# IFX9201_Core.net
KiCad netlist of a schematic drawn in Altium Designer
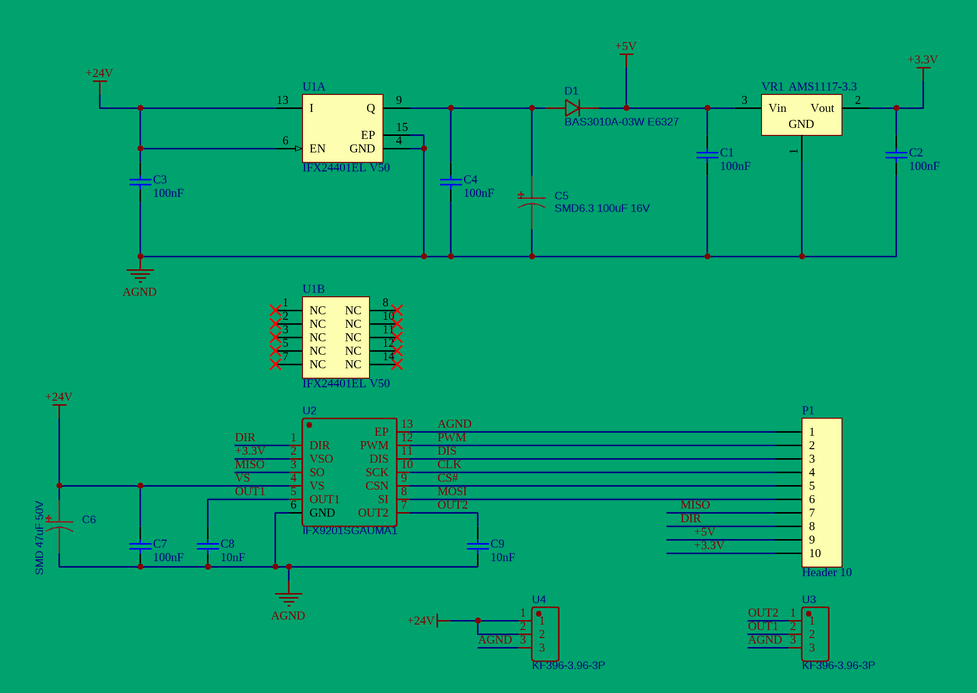
[diagram p0: IFX9201_Core.SchDoc]

(export (version "E")
  (design (tool "Eeschema 10.0.6"))
  (components
    (comp (ref "C1")
      (value "100nF")
      (footprint "0603_C")
      (description "GCJ188R72A104KA01D")
      (libsource (lib "Miscellaneous Devices LC") (part "0603 2.7nF (272) 10% 50V"))
    )
    (comp (ref "C2")
      (value "100nF")
      (footprint "0603_C")
      (description "GCJ188R72A104KA01D")
      (libsource (lib "Miscellaneous Devices LC") (part "0603 2.7nF (272) 10% 50V"))
    )
    (comp (ref "C3")
      (value "100nF")
      (footprint "0603_C")
      (description "GCJ188R72A104KA01D")
      (libsource (lib "Miscellaneous Devices LC") (part "0603 2.7nF (272) 10% 50V"))
    )
    (comp (ref "C4")
      (value "100nF")
      (footprint "0603_C")
      (description "GCJ188R72A104KA01D")
      (libsource (lib "Miscellaneous Devices LC") (part "0603 2.7nF (272) 10% 50V"))
    )
    (comp (ref "C5")
      (value "SMD6.3 100uF 16V")
      (footprint "CAP-SMD_BD6.3-L6.6-W6.6-FD")
      (description "UUD1C101MCL1GS")
      (libsource (lib "Miscellaneous Devices LC") (part "SMD6.3 100uF"))
    )
    (comp (ref "C6")
      (value "SMD 47uF 50V")
      (footprint "CAP-SMD_BD6.3-L6.6-W6.6-FD")
      (description "EEEFT1H470AP")
      (libsource (lib "Miscellaneous Devices LC") (part "SMD6.3 100uF"))
    )
    (comp (ref "C7")
      (value "100nF")
      (footprint "0603_C")
      (description "GCJ188R72A104KA01D")
      (libsource (lib "Miscellaneous Devices LC") (part "0603 2.7nF (272) 10% 50V"))
    )
    (comp (ref "C8")
      (value "10nF")
      (footprint "0603_C")
      (description "GCM188R72A103KA37D")
      (libsource (lib "Miscellaneous Devices LC") (part "0603 2.7nF (272) 10% 50V"))
    )
    (comp (ref "C9")
      (value "10nF")
      (footprint "0603_C")
      (description "GCM188R72A103KA37D")
      (libsource (lib "Miscellaneous Devices LC") (part "0603 2.7nF (272) 10% 50V"))
    )
    (comp (ref "D1")
      (value "BAS3010A-03W E6327")
      (footprint "SOD-323_L1.8-W1.3-LS2.5-RD")
      (fields (field (name "BOM_MANUFACTURER PART") "BAS 3010A-03W E6327"))
      (libsource (lib "Miscellaneous Devices LC") (part "BAS3010A-03W E6327"))
    )
    (comp (ref "P1")
      (value "Header 10")
      (footprint "HDR1X10")
      (description "Header, 10-Pin")
      (fields (field (name "PUBLISHER") "Altium Limited"))
      (libsource (lib "Miscellaneous Connectors") (part "Header 10"))
    )
    (comp (ref "U1")
      (value "IFX24401EL V50")
      (footprint "INF-PG-SSOP-14-1_N")
      (fields (field (name "MANUFACTURER") "Infineon"))
      (libsource (lib "Infineon_Power_Supply_Voltage_Regulator") (part "IFX24401EL V50"))
    )
    (comp (ref "U2")
      (value "IFX9201SGAUMA1")
      (footprint "SO-12_L6.4-W7.5-P1.00-LS10.3-BL-EP")
      (libsource (lib "Miscellaneous Devices LC") (part "IFX9201SGAUMA1"))
    )
    (comp (ref "U3")
      (value "KF396-3.96-3P")
      (footprint "CONN-TH_3P-P3.96_KF396-3.96-3P")
      (fields (field (name "BOM_SUPPLIER PART") "C474895") (field (name "CONTRIBUTOR") "LCSC"))
      (libsource (lib "Miscellaneous Devices LC") (part "KF396-3.96-3P"))
    )
    (comp (ref "U4")
      (value "KF396-3.96-3P")
      (footprint "CONN-TH_3P-P3.96_KF396-3.96-3P")
      (fields (field (name "BOM_SUPPLIER PART") "C474895") (field (name "CONTRIBUTOR") "LCSC"))
      (libsource (lib "Miscellaneous Devices LC") (part "KF396-3.96-3P"))
    )
    (comp (ref "VR1")
      (value "AMS1117-3.3")
      (footprint "SOT-223")
      (description "低压差线性稳压(LDO)")
      (libsource (lib "Miscellaneous Devices LC") (part "SOT-223 AMS1117-3.3"))
    )
  )
  (nets
    (net (code "1") (name "+3.3V") (class "Default")
      (node (ref "C2") (pin "2") (pinfunction "2_2") (pintype "passive"))
      (node (ref "P1") (pin "10") (pinfunction "10_10") (pintype "passive"))
      (node (ref "U2") (pin "2") (pinfunction "VSO_2") (pintype "passive"))
      (node (ref "VR1") (pin "2") (pinfunction "Vout_2") (pintype "passive"))
    )
    (net (code "2") (name "+5V") (class "Default")
      (node (ref "C1") (pin "2") (pinfunction "2_2") (pintype "passive"))
      (node (ref "D1") (pin "1") (pinfunction "C_1") (pintype "passive"))
      (node (ref "P1") (pin "9") (pinfunction "9_9") (pintype "passive"))
      (node (ref "VR1") (pin "3") (pinfunction "Vin_3") (pintype "passive"))
    )
    (net (code "3") (name "+24V") (class "Default")
      (node (ref "C3") (pin "2") (pinfunction "2_2") (pintype "passive"))
      (node (ref "C6") (pin "1") (pinfunction "1_1") (pintype "passive"))
      (node (ref "C7") (pin "2") (pinfunction "2_2") (pintype "passive"))
      (node (ref "U1") (pin "13") (pinfunction "I_13") (pintype "power_in"))
      (node (ref "U1") (pin "6") (pinfunction "EN_6") (pintype "input"))
      (node (ref "U2") (pin "4") (pinfunction "VS_4") (pintype "passive"))
      (node (ref "U4") (pin "1") (pinfunction "1_1") (pintype "passive"))
      (node (ref "U4") (pin "2") (pinfunction "2_2") (pintype "passive"))
    )
    (net (code "4") (name "/CLK") (class "Default")
      (node (ref "P1") (pin "4") (pinfunction "4_4") (pintype "passive"))
      (node (ref "U2") (pin "10") (pinfunction "SCK_10") (pintype "passive"))
    )
    (net (code "5") (name "/CS#") (class "Default")
      (node (ref "P1") (pin "5") (pinfunction "5_5") (pintype "passive"))
      (node (ref "U2") (pin "9") (pinfunction "CSN_9") (pintype "passive"))
    )
    (net (code "6") (name "/DIR") (class "Default")
      (node (ref "P1") (pin "8") (pinfunction "8_8") (pintype "passive"))
      (node (ref "U2") (pin "1") (pinfunction "DIR_1") (pintype "passive"))
    )
    (net (code "7") (name "/DIS") (class "Default")
      (node (ref "P1") (pin "3") (pinfunction "3_3") (pintype "passive"))
      (node (ref "U2") (pin "11") (pinfunction "DIS_11") (pintype "passive"))
    )
    (net (code "8") (name "/MISO") (class "Default")
      (node (ref "P1") (pin "7") (pinfunction "7_7") (pintype "passive"))
      (node (ref "U2") (pin "3") (pinfunction "SO_3") (pintype "passive"))
    )
    (net (code "9") (name "/MOSI") (class "Default")
      (node (ref "P1") (pin "6") (pinfunction "6_6") (pintype "passive"))
      (node (ref "U2") (pin "8") (pinfunction "SI_8") (pintype "passive"))
    )
    (net (code "10") (name "/OUT1") (class "Default")
      (node (ref "C8") (pin "2") (pinfunction "2_2") (pintype "passive"))
      (node (ref "U2") (pin "5") (pinfunction "OUT1_5") (pintype "passive"))
      (node (ref "U3") (pin "2") (pinfunction "2_2") (pintype "passive"))
    )
    (net (code "11") (name "/OUT2") (class "Default")
      (node (ref "C9") (pin "2") (pinfunction "2_2") (pintype "passive"))
      (node (ref "U2") (pin "7") (pinfunction "OUT2_7") (pintype "passive"))
      (node (ref "U3") (pin "1") (pinfunction "1_1") (pintype "passive"))
    )
    (net (code "12") (name "/PWM") (class "Default")
      (node (ref "P1") (pin "2") (pinfunction "2_2") (pintype "passive"))
      (node (ref "U2") (pin "12") (pinfunction "PWM_12") (pintype "passive"))
    )
    (net (code "13") (name "AGND") (class "Default")
      (node (ref "C1") (pin "1") (pinfunction "1_1") (pintype "passive"))
      (node (ref "C2") (pin "1") (pinfunction "1_1") (pintype "passive"))
      (node (ref "C3") (pin "1") (pinfunction "1_1") (pintype "passive"))
      (node (ref "C4") (pin "1") (pinfunction "1_1") (pintype "passive"))
      (node (ref "C5") (pin "2") (pinfunction "2_2") (pintype "passive"))
      (node (ref "C6") (pin "2") (pinfunction "2_2") (pintype "passive"))
      (node (ref "C7") (pin "1") (pinfunction "1_1") (pintype "passive"))
      (node (ref "C8") (pin "1") (pinfunction "1_1") (pintype "passive"))
      (node (ref "C9") (pin "1") (pinfunction "1_1") (pintype "passive"))
      (node (ref "P1") (pin "1") (pinfunction "1_1") (pintype "passive"))
      (node (ref "U1") (pin "15") (pinfunction "EP_15") (pintype "power_in"))
      (node (ref "U1") (pin "4") (pinfunction "GND_4") (pintype "power_in"))
      (node (ref "U2") (pin "13") (pinfunction "EP_13") (pintype "passive"))
      (node (ref "U2") (pin "6") (pinfunction "GND_6") (pintype "passive"))
      (node (ref "U3") (pin "3") (pinfunction "3_3") (pintype "passive"))
      (node (ref "U4") (pin "3") (pinfunction "3_3") (pintype "passive"))
      (node (ref "VR1") (pin "1") (pinfunction "GND_1") (pintype "passive"))
    )
    (net (code "14") (name "Net-(D1-A)") (class "Default")
      (node (ref "C4") (pin "2") (pinfunction "2_2") (pintype "passive"))
      (node (ref "C5") (pin "1") (pinfunction "1_1") (pintype "passive"))
      (node (ref "D1") (pin "2") (pinfunction "A_2") (pintype "passive"))
      (node (ref "U1") (pin "9") (pinfunction "Q_9") (pintype "power_in"))
    )
    (net (code "15") (name "unconnected-(U1B-NC-Pad1)") (class "Default")
      (node (ref "U1") (pin "1") (pinfunction "NC_1") (pintype "passive+no_connect"))
    )
    (net (code "16") (name "unconnected-(U1B-NC-Pad2)") (class "Default")
      (node (ref "U1") (pin "2") (pinfunction "NC_2") (pintype "passive+no_connect"))
    )
    (net (code "17") (name "unconnected-(U1B-NC-Pad3)") (class "Default")
      (node (ref "U1") (pin "3") (pinfunction "NC_3") (pintype "passive+no_connect"))
    )
    (net (code "18") (name "unconnected-(U1B-NC-Pad5)") (class "Default")
      (node (ref "U1") (pin "5") (pinfunction "NC_5") (pintype "passive+no_connect"))
    )
    (net (code "19") (name "unconnected-(U1B-NC-Pad7)") (class "Default")
      (node (ref "U1") (pin "7") (pinfunction "NC_7") (pintype "passive+no_connect"))
    )
    (net (code "20") (name "unconnected-(U1B-NC-Pad8)") (class "Default")
      (node (ref "U1") (pin "8") (pinfunction "NC_8") (pintype "passive+no_connect"))
    )
    (net (code "21") (name "unconnected-(U1B-NC-Pad10)") (class "Default")
      (node (ref "U1") (pin "10") (pinfunction "NC_10") (pintype "passive+no_connect"))
    )
    (net (code "22") (name "unconnected-(U1B-NC-Pad11)") (class "Default")
      (node (ref "U1") (pin "11") (pinfunction "NC_11") (pintype "passive+no_connect"))
    )
    (net (code "23") (name "unconnected-(U1B-NC-Pad12)") (class "Default")
      (node (ref "U1") (pin "12") (pinfunction "NC_12") (pintype "passive+no_connect"))
    )
    (net (code "24") (name "unconnected-(U1B-NC-Pad14)") (class "Default")
      (node (ref "U1") (pin "14") (pinfunction "NC_14") (pintype "passive+no_connect"))
    )
  )
)
